# LTC4359_28V_5A.net
KiCad netlist of a schematic drawn in Altium Designer
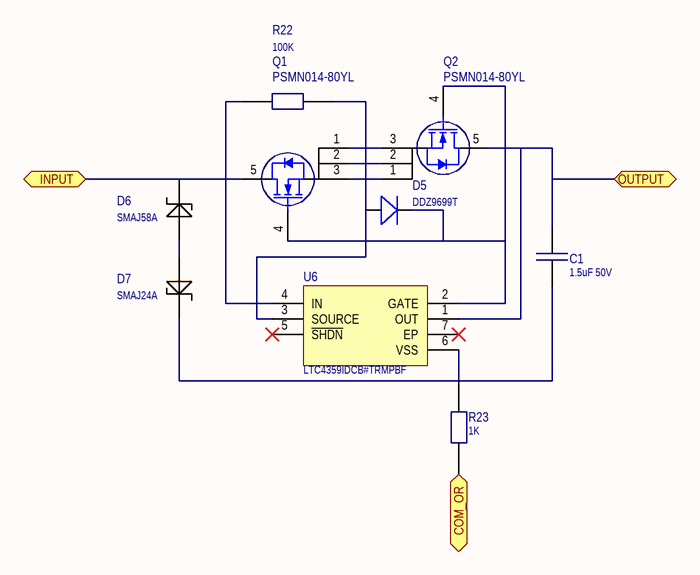
[diagram p0: LTC4359_28V_5A.schdoc]

(export (version "E")
  (design (tool "Eeschema 10.0.6"))
  (components
    (comp (ref "C1")
      (value "1.5uF 50V")
      (footprint "C_0805")
      (description "Capacitor")
      (libsource (lib "capacitors") (part "C0805"))
    )
    (comp (ref "D5")
      (value "DDZ9699T")
      (footprint "SOD523F - 2")
      (description "Diode")
      (libsource (lib "diode") (part "D_SOD523"))
    )
    (comp (ref "D6")
      (value "SMAJ58A")
      (footprint "DO-214AC")
      (description "Diode")
      (libsource (lib "diode") (part "D_DO-214AC"))
    )
    (comp (ref "D7")
      (value "SMAJ24A")
      (footprint "DO-214AC")
      (description "Diode")
      (libsource (lib "diode") (part "D_DO-214AC"))
    )
    (comp (ref "Q1")
      (value "PSMN014-80YL")
      (footprint "SOT669_LFPAK56; Power-SO8")
      (description "Power MOSFET")
      (libsource (lib "transistors") (part "N-ch SOT669/LFPAK56"))
    )
    (comp (ref "Q2")
      (value "PSMN014-80YL")
      (footprint "SOT669_LFPAK56; Power-SO8")
      (description "Power MOSFET")
      (libsource (lib "transistors") (part "N-ch SOT669/LFPAK56"))
    )
    (comp (ref "R22")
      (value "100K")
      (footprint "R_0603")
      (description "Resistor")
      (libsource (lib "resistors") (part "R0603"))
    )
    (comp (ref "R23")
      (value "1K")
      (footprint "R_0805")
      (description "Resistor")
      (libsource (lib "resistors") (part "R0805"))
    )
    (comp (ref "U6")
      (value "LTC4359IDCB#TRMPBF")
      (footprint "LT-DCB-6_V")
      (description "ideal diode ic")
      (libsource (lib "analog_ic") (part "LTC4359IDCB#TRMPBF"))
    )
  )
  (nets
    (net (code "1") (name "/COM_OR") (class "Default")
      (node (ref "R23") (pin "1") (pinfunction "1_1") (pintype "passive"))
    )
    (net (code "2") (name "/INPUT") (class "Default")
      (node (ref "D6") (pin "2") (pinfunction "K_2") (pintype "passive"))
      (node (ref "Q1") (pin "5") (pinfunction "D_5") (pintype "passive"))
      (node (ref "R22") (pin "1") (pinfunction "1_1") (pintype "passive"))
      (node (ref "U6") (pin "4") (pinfunction "IN_4") (pintype "passive"))
    )
    (net (code "3") (name "/OUTPUT") (class "Default")
      (node (ref "C1") (pin "2") (pinfunction "2_2") (pintype "passive"))
      (node (ref "Q2") (pin "5") (pinfunction "D_5") (pintype "passive"))
      (node (ref "U6") (pin "1") (pinfunction "OUT_1") (pintype "passive"))
    )
    (net (code "4") (name "Net-(D5-A)") (class "Default")
      (node (ref "D5") (pin "1") (pinfunction "A_1") (pintype "passive"))
      (node (ref "Q1") (pin "1") (pinfunction "S_1") (pintype "passive"))
      (node (ref "Q1") (pin "2") (pinfunction "S_2") (pintype "passive"))
      (node (ref "Q1") (pin "3") (pinfunction "S_3") (pintype "passive"))
      (node (ref "Q2") (pin "1") (pinfunction "S_1") (pintype "passive"))
      (node (ref "Q2") (pin "2") (pinfunction "S_2") (pintype "passive"))
      (node (ref "Q2") (pin "3") (pinfunction "S_3") (pintype "passive"))
      (node (ref "R22") (pin "2") (pinfunction "2_2") (pintype "passive"))
      (node (ref "U6") (pin "3") (pinfunction "SOURCE_3") (pintype "passive"))
    )
    (net (code "5") (name "Net-(D5-K)") (class "Default")
      (node (ref "D5") (pin "2") (pinfunction "K_2") (pintype "passive"))
      (node (ref "Q1") (pin "4") (pinfunction "G_4") (pintype "passive"))
      (node (ref "Q2") (pin "4") (pinfunction "G_4") (pintype "passive"))
      (node (ref "U6") (pin "2") (pinfunction "GATE_2") (pintype "passive"))
    )
    (net (code "6") (name "Net-(D6-A)") (class "Default")
      (node (ref "D6") (pin "1") (pinfunction "A_1") (pintype "passive"))
      (node (ref "D7") (pin "1") (pinfunction "A_1") (pintype "passive"))
    )
    (net (code "7") (name "Net-(D7-K)") (class "Default")
      (node (ref "C1") (pin "1") (pinfunction "1_1") (pintype "passive"))
      (node (ref "D7") (pin "2") (pinfunction "K_2") (pintype "passive"))
      (node (ref "R23") (pin "2") (pinfunction "2_2") (pintype "passive"))
      (node (ref "U6") (pin "6") (pinfunction "VSS_6") (pintype "passive"))
    )
    (net (code "8") (name "unconnected-(U6-EP-Pad7)") (class "Default")
      (node (ref "U6") (pin "7") (pinfunction "EP_7") (pintype "passive+no_connect"))
    )
    (net (code "9") (name "unconnected-(U6-~{SHDN}-Pad5)") (class "Default")
      (node (ref "U6") (pin "5") (pinfunction "~{SHDN}_5") (pintype "passive+no_connect"))
    )
  )
)
